# EasyEDA_SCH_smart-led.net
KiCad netlist of a schematic drawn in EasyEDA
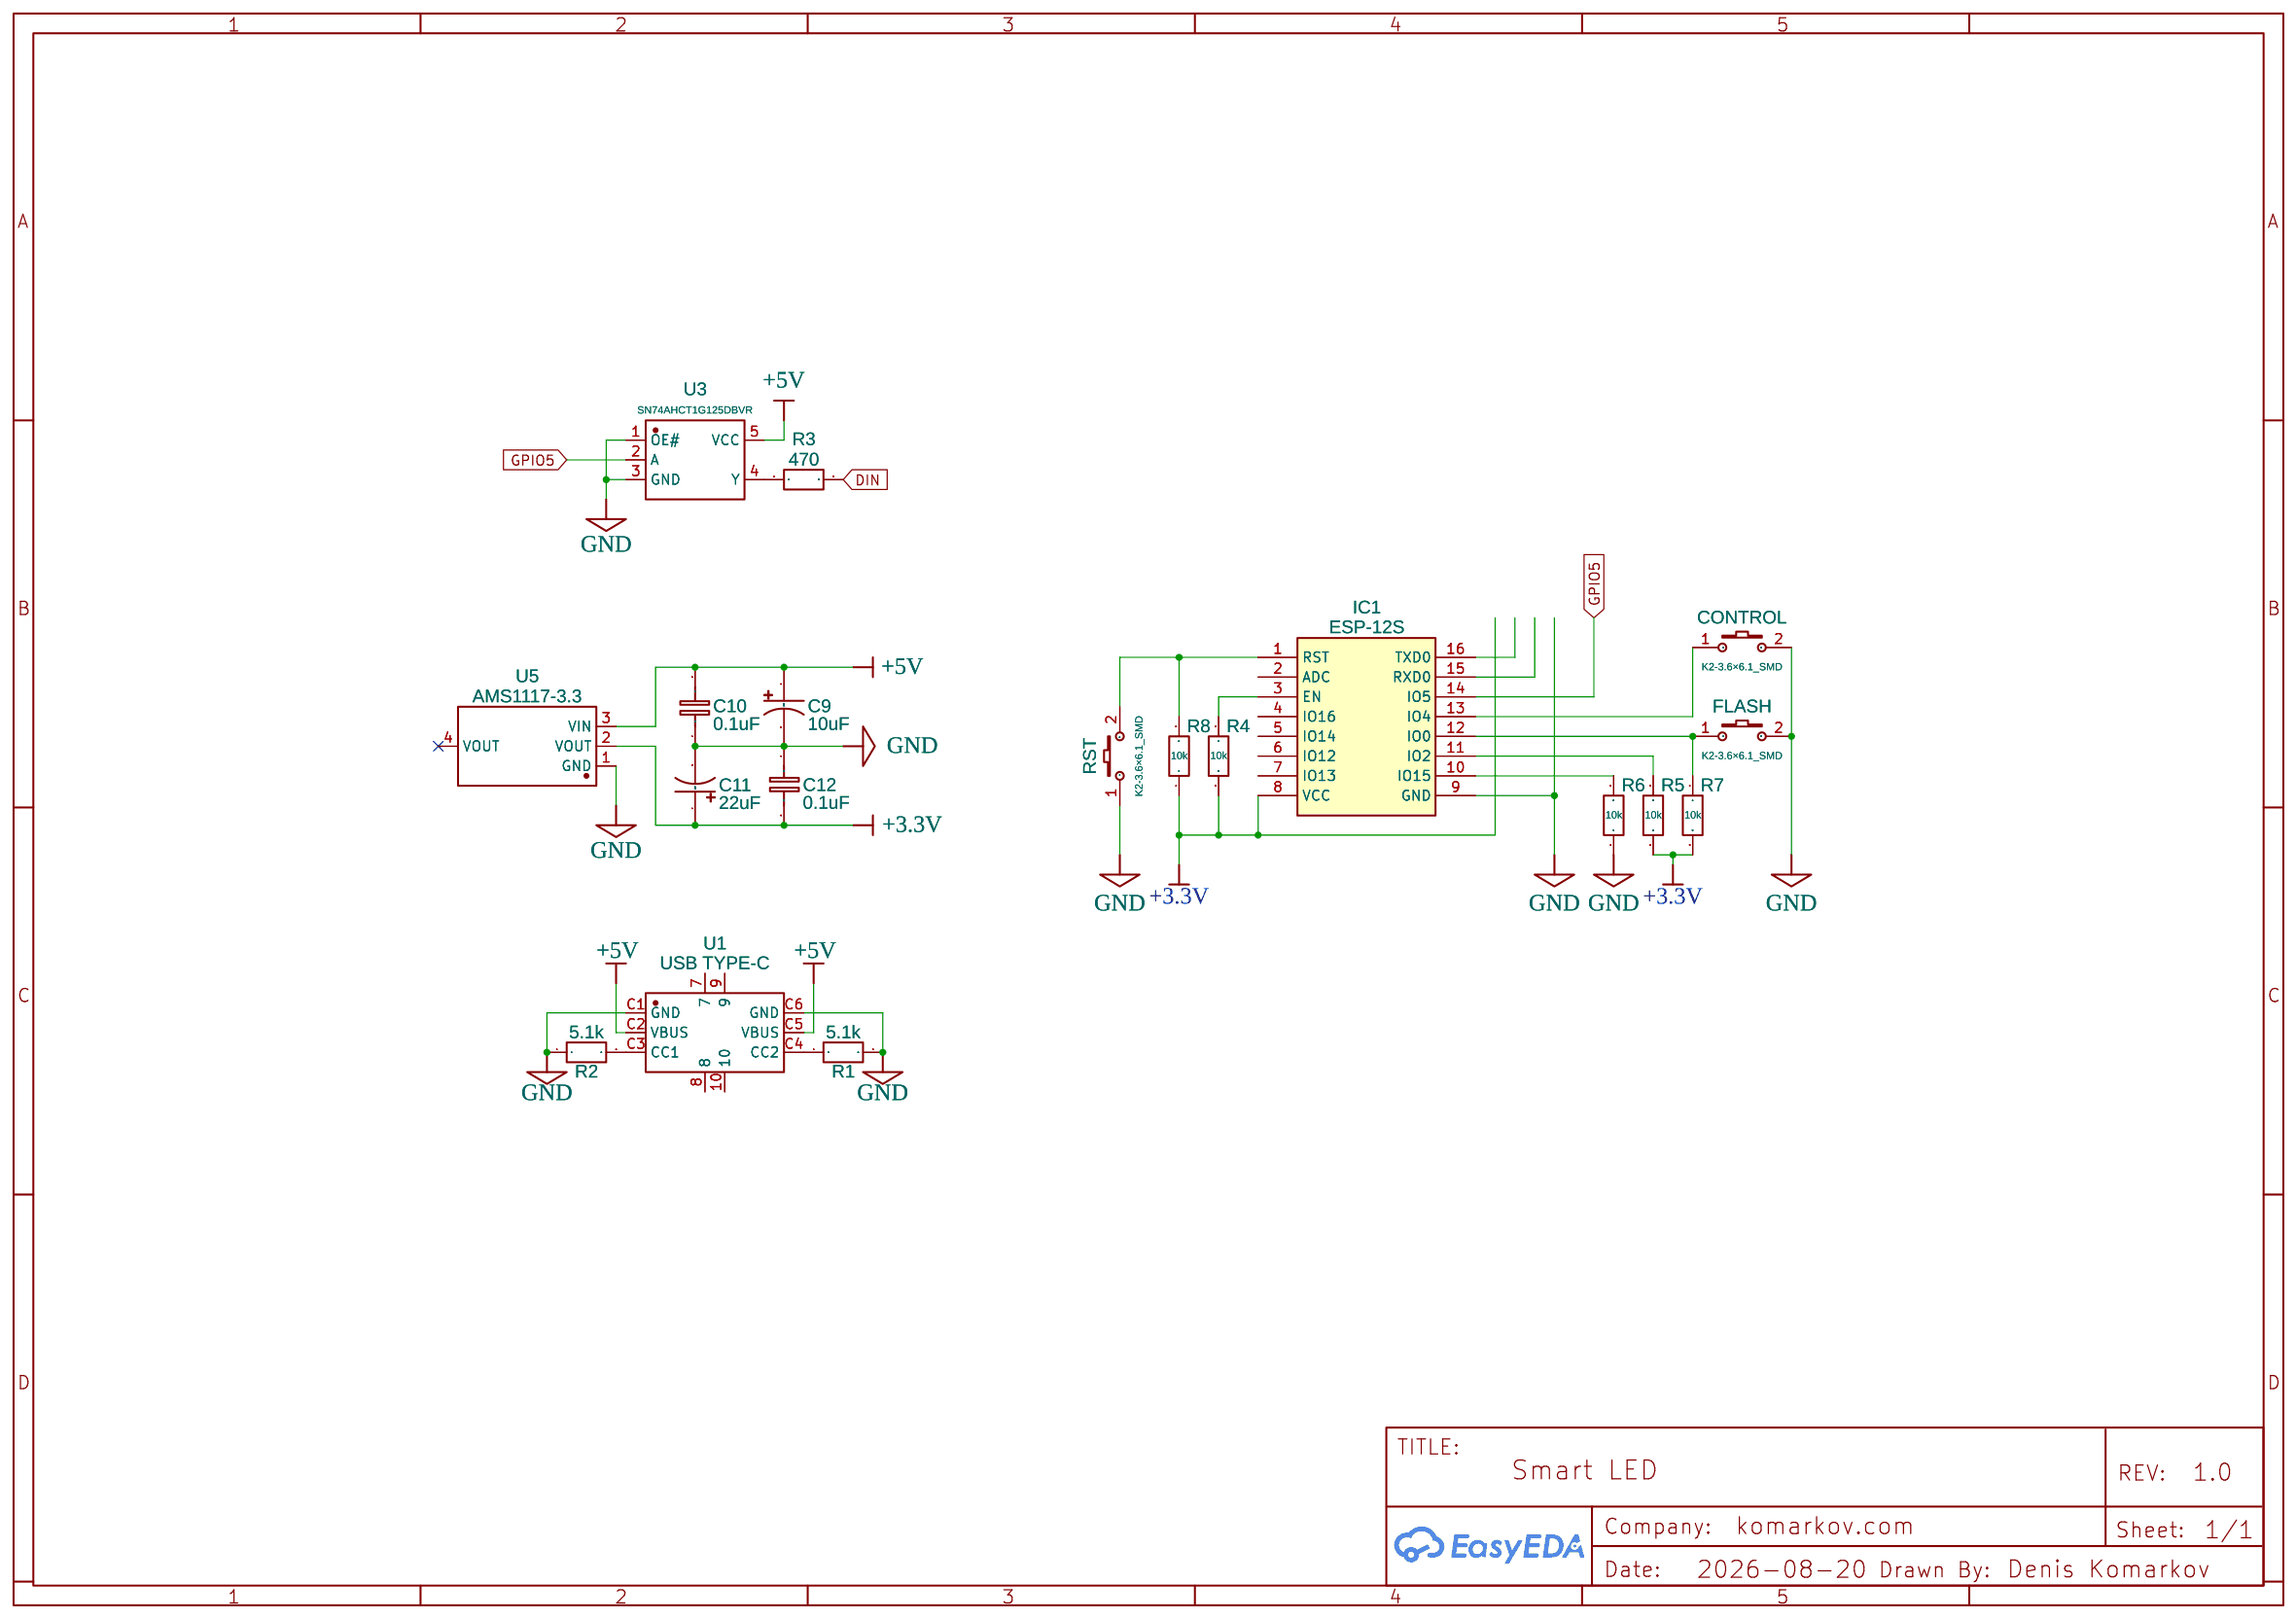
[diagram p0: schematic sheet]

(export (version "E")
  (design (tool "Eeschema 10.0.6"))
  (components
    (comp (ref "C9")
      (value "10uF")
      (fields (field (name "Manufacturer Part") "EEEFC1C100AR") (field (name "Manufacturer") "PANASONIC(松下)"))
      (libsource (lib "") (part "EEEFC1C100AR"))
    )
    (comp (ref "C10") (value "0.1uF") (libsource (lib "") (part "C_0805_EU_1")))
    (comp (ref "C11")
      (value "22uF")
      (fields (field (name "Manufacturer Part") "EEEFC1C220AR") (field (name "Manufacturer") "PANASONIC(松下)"))
      (libsource (lib "") (part "EEEFC1C220AR"))
    )
    (comp (ref "C12") (value "0.1uF") (libsource (lib "") (part "C_0805_EU")))
    (comp (ref "CONTROL")
      (value "K2-3.6×6.1_SMD")
      (fields (field (name "Manufacturer Part") "K2-1107ST-A4SW-06"))
      (libsource (lib "") (part "K2-3.6×6.1_SMD"))
    )
    (comp (ref "FLASH")
      (value "K2-3.6×6.1_SMD")
      (fields (field (name "Manufacturer Part") "K2-1107ST-A4SW-06"))
      (libsource (lib "") (part "K2-3.6×6.1_SMD_1"))
    )
    (comp (ref "IC1") (value "ESP-12S") (libsource (lib "") (part "ESP-12S")))
    (comp (ref "R1") (value "5.1k") (libsource (lib "") (part "R_1206_EU")))
    (comp (ref "R2") (value "5.1k") (libsource (lib "") (part "R_1206_EU")))
    (comp (ref "R3") (value "470") (libsource (lib "") (part "R_1206_EU")))
    (comp (ref "R4") (value "10k") (libsource (lib "") (part "R_0805_EU")))
    (comp (ref "R5") (value "10k") (libsource (lib "") (part "R_0805_EU_1")))
    (comp (ref "R6") (value "10k") (libsource (lib "") (part "R_0805_EU_1")))
    (comp (ref "R7") (value "10k") (libsource (lib "") (part "R_0805_EU")))
    (comp (ref "R8") (value "10k") (libsource (lib "") (part "R_0805_EU_1")))
    (comp (ref "RST")
      (value "K2-3.6×6.1_SMD")
      (fields (field (name "Manufacturer Part") "K2-1107ST-A4SW-06"))
      (libsource (lib "") (part "K2-3.6×6.1_SMD_2"))
    )
    (comp (ref "U1")
      (value "USB TYPE-C")
      (fields (field (name "Manufacturer Part") "USB3.1 TYPE-C 06PF-073"))
      (libsource (lib "") (part "USB3.1 TYPE-C 06PF-073"))
    )
    (comp (ref "U3")
      (value "SN74AHCT1G125DBVR")
      (fields (field (name "Manufacturer") "TI(德州仪器)"))
      (libsource (lib "") (part "SN74AHCT1G125DBVR"))
    )
    (comp (ref "U5")
      (value "AMS1117-3.3")
      (fields (field (name "Manufacturer") "AMS"))
      (libsource (lib "") (part "AMS1117-3.3"))
    )
  )
  (nets
    (net (code "1") (name "+3.3V") (class "Default")
      (node (ref "C11") (pin "1") (pinfunction "1_1") (pintype "unspecified"))
      (node (ref "C12") (pin "2") (pinfunction "2_2") (pintype "unspecified"))
      (node (ref "IC1") (pin "8") (pinfunction "VCC_8") (pintype "unspecified"))
      (node (ref "R4") (pin "2") (pinfunction "2_2") (pintype "unspecified"))
      (node (ref "R5") (pin "1") (pinfunction "1_1") (pintype "unspecified"))
      (node (ref "R7") (pin "2") (pinfunction "2_2") (pintype "unspecified"))
      (node (ref "R8") (pin "1") (pinfunction "1_1") (pintype "unspecified"))
      (node (ref "U5") (pin "2") (pinfunction "VOUT_2") (pintype "unspecified"))
    )
    (net (code "2") (name "+5V") (class "Default")
      (node (ref "C10") (pin "2") (pinfunction "2_2") (pintype "unspecified"))
      (node (ref "C9") (pin "1") (pinfunction "1_1") (pintype "unspecified"))
      (node (ref "U1") (pin "C2") (pinfunction "VBUS_C2") (pintype "unspecified"))
      (node (ref "U1") (pin "C5") (pinfunction "VBUS_C5") (pintype "unspecified"))
      (node (ref "U3") (pin "5") (pinfunction "VCC_5") (pintype "unspecified"))
      (node (ref "U5") (pin "3") (pinfunction "VIN_3") (pintype "unspecified"))
    )
    (net (code "3") (name "DIN") (class "Default")
      (node (ref "R3") (pin "2") (pinfunction "2_2") (pintype "unspecified"))
    )
    (net (code "4") (name "GND") (class "Default")
      (node (ref "C10") (pin "1") (pinfunction "1_1") (pintype "unspecified"))
      (node (ref "C11") (pin "2") (pinfunction "2_2") (pintype "unspecified"))
      (node (ref "C12") (pin "1") (pinfunction "1_1") (pintype "unspecified"))
      (node (ref "C9") (pin "2") (pinfunction "2_2") (pintype "unspecified"))
      (node (ref "CONTROL") (pin "2") (pinfunction "2_2") (pintype "unspecified"))
      (node (ref "FLASH") (pin "2") (pinfunction "2_2") (pintype "unspecified"))
      (node (ref "IC1") (pin "9") (pinfunction "GND_9") (pintype "unspecified"))
      (node (ref "R1") (pin "2") (pinfunction "2_2") (pintype "unspecified"))
      (node (ref "R2") (pin "1") (pinfunction "1_1") (pintype "unspecified"))
      (node (ref "R6") (pin "1") (pinfunction "1_1") (pintype "unspecified"))
      (node (ref "RST") (pin "1") (pinfunction "1_1") (pintype "unspecified"))
      (node (ref "U1") (pin "C1") (pinfunction "GND_C1") (pintype "unspecified"))
      (node (ref "U1") (pin "C6") (pinfunction "GND_C6") (pintype "unspecified"))
      (node (ref "U3") (pin "1") (pinfunction "OE#_1") (pintype "unspecified"))
      (node (ref "U3") (pin "3") (pinfunction "GND_3") (pintype "unspecified"))
      (node (ref "U5") (pin "1") (pinfunction "GND_1") (pintype "unspecified"))
    )
    (net (code "5") (name "GPIO5") (class "Default")
      (node (ref "IC1") (pin "14") (pinfunction "IO5_14") (pintype "unspecified"))
      (node (ref "U3") (pin "2") (pinfunction "A_2") (pintype "unspecified"))
    )
    (net (code "6") (name "Net-(IC1-EN)") (class "Default")
      (node (ref "IC1") (pin "3") (pinfunction "EN_3") (pintype "unspecified"))
      (node (ref "R4") (pin "1") (pinfunction "1_1") (pintype "unspecified"))
    )
    (net (code "7") (name "Net-(IC1-IO0)") (class "Default")
      (node (ref "FLASH") (pin "1") (pinfunction "1_1") (pintype "unspecified"))
      (node (ref "IC1") (pin "12") (pinfunction "IO0_12") (pintype "unspecified"))
      (node (ref "R7") (pin "1") (pinfunction "1_1") (pintype "unspecified"))
    )
    (net (code "8") (name "Net-(IC1-IO2)") (class "Default")
      (node (ref "IC1") (pin "11") (pinfunction "IO2_11") (pintype "unspecified"))
      (node (ref "R5") (pin "2") (pinfunction "2_2") (pintype "unspecified"))
    )
    (net (code "9") (name "Net-(IC1-IO4)") (class "Default")
      (node (ref "CONTROL") (pin "1") (pinfunction "1_1") (pintype "unspecified"))
      (node (ref "IC1") (pin "13") (pinfunction "IO4_13") (pintype "unspecified"))
    )
    (net (code "10") (name "Net-(IC1-IO15)") (class "Default")
      (node (ref "IC1") (pin "10") (pinfunction "IO15_10") (pintype "unspecified"))
      (node (ref "R6") (pin "2") (pinfunction "2_2") (pintype "unspecified"))
    )
    (net (code "11") (name "Net-(IC1-RST)") (class "Default")
      (node (ref "IC1") (pin "1") (pinfunction "RST_1") (pintype "unspecified"))
      (node (ref "R8") (pin "2") (pinfunction "2_2") (pintype "unspecified"))
      (node (ref "RST") (pin "2") (pinfunction "2_2") (pintype "unspecified"))
    )
    (net (code "12") (name "Net-(U1-CC1)") (class "Default")
      (node (ref "R2") (pin "2") (pinfunction "2_2") (pintype "unspecified"))
      (node (ref "U1") (pin "C3") (pinfunction "CC1_C3") (pintype "unspecified"))
    )
    (net (code "13") (name "Net-(U1-CC2)") (class "Default")
      (node (ref "R1") (pin "1") (pinfunction "1_1") (pintype "unspecified"))
      (node (ref "U1") (pin "C4") (pinfunction "CC2_C4") (pintype "unspecified"))
    )
    (net (code "14") (name "Net-(U3-Y)") (class "Default")
      (node (ref "R3") (pin "1") (pinfunction "1_1") (pintype "unspecified"))
      (node (ref "U3") (pin "4") (pinfunction "Y_4") (pintype "unspecified"))
    )
    (net (code "15") (name "unconnected-(IC1-ADC-Pad2)") (class "Default")
      (node (ref "IC1") (pin "2") (pinfunction "ADC_2") (pintype "unspecified"))
    )
    (net (code "16") (name "unconnected-(IC1-IO12-Pad6)") (class "Default")
      (node (ref "IC1") (pin "6") (pinfunction "IO12_6") (pintype "unspecified"))
    )
    (net (code "17") (name "unconnected-(IC1-IO13-Pad7)") (class "Default")
      (node (ref "IC1") (pin "7") (pinfunction "IO13_7") (pintype "unspecified"))
    )
    (net (code "18") (name "unconnected-(IC1-IO14-Pad5)") (class "Default")
      (node (ref "IC1") (pin "5") (pinfunction "IO14_5") (pintype "unspecified"))
    )
    (net (code "19") (name "unconnected-(IC1-IO16-Pad4)") (class "Default")
      (node (ref "IC1") (pin "4") (pinfunction "IO16_4") (pintype "unspecified"))
    )
    (net (code "20") (name "unconnected-(IC1-RXD0-Pad15)") (class "Default")
      (node (ref "IC1") (pin "15") (pinfunction "RXD0_15") (pintype "unspecified"))
    )
    (net (code "21") (name "unconnected-(IC1-TXD0-Pad16)") (class "Default")
      (node (ref "IC1") (pin "16") (pinfunction "TXD0_16") (pintype "unspecified"))
    )
    (net (code "22") (name "unconnected-(U1-Pad7)") (class "Default")
      (node (ref "U1") (pin "7") (pinfunction "7_7") (pintype "unspecified"))
    )
    (net (code "23") (name "unconnected-(U1-Pad8)") (class "Default")
      (node (ref "U1") (pin "8") (pinfunction "8_8") (pintype "unspecified"))
    )
    (net (code "24") (name "unconnected-(U1-Pad9)") (class "Default")
      (node (ref "U1") (pin "9") (pinfunction "9_9") (pintype "unspecified"))
    )
    (net (code "25") (name "unconnected-(U1-Pad10)") (class "Default")
      (node (ref "U1") (pin "10") (pinfunction "10_10") (pintype "unspecified"))
    )
    (net (code "26") (name "unconnected-(U5-VOUT-Pad4)") (class "Default")
      (node (ref "U5") (pin "4") (pinfunction "VOUT_4") (pintype "unspecified+no_connect"))
    )
  )
)
